# Sheet.net
KiCad netlist of a schematic drawn in Altium Designer
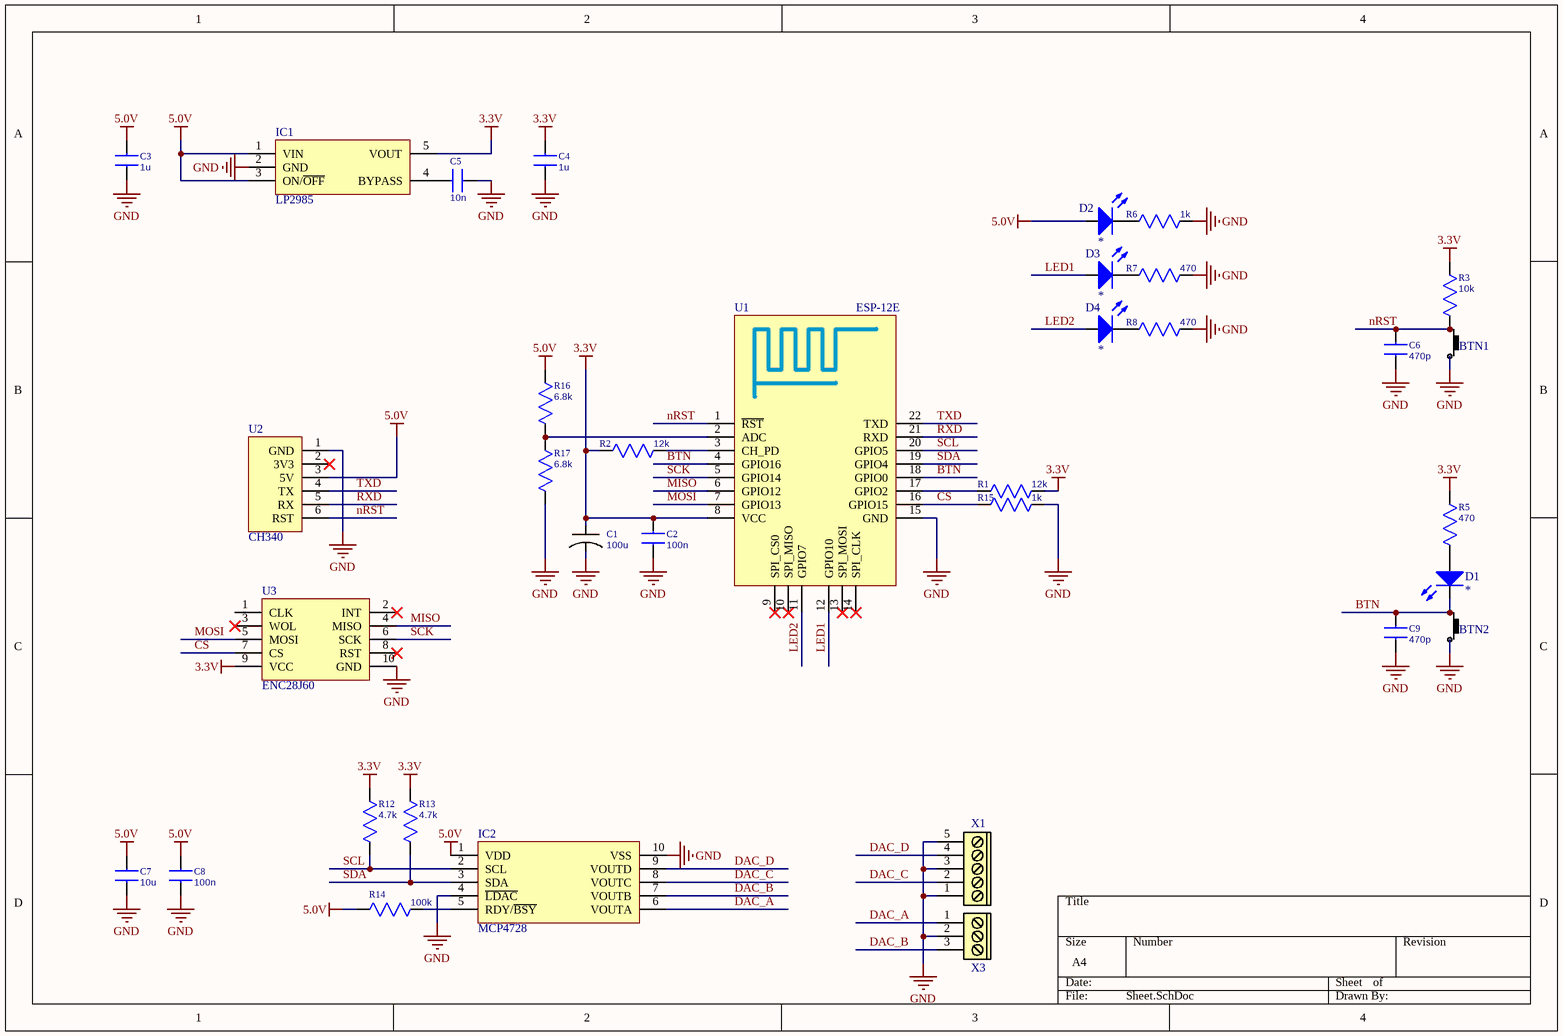
[diagram p0: Sheet.SchDoc]

(export (version "E")
  (design (tool "Eeschema 10.0.6"))
  (components
    (comp (ref "BTN1")
      (value "Push Button")
      (footprint "PUSH BUTTON RIGHT ANGLE")
      (description "Push button")
      (libsource (lib "Light_Music_Integrated_Library") (part "Push Button"))
    )
    (comp (ref "BTN2")
      (value "Push Button")
      (footprint "PUSH BUTTON RIGHT ANGLE")
      (description "Push button")
      (libsource (lib "") (part "Push Button_1"))
    )
    (comp (ref "C1")
      (value "100u")
      (footprint "R79")
      (description "Electrolit capasitor")
      (libsource (lib "SmartOutletIntegratedLibrary") (part "Electrolit"))
    )
    (comp (ref "C2")
      (value "100n")
      (footprint "C_0603")
      (description "Capacitor")
      (libsource (lib "AX_Altium_v2.3") (part "C0603"))
    )
    (comp (ref "C3")
      (value "1u")
      (footprint "C_0805")
      (description "Capacitor")
      (libsource (lib "AX_Altium_v2.3") (part "C0805"))
    )
    (comp (ref "C4")
      (value "1u")
      (footprint "C_0805")
      (description "Capacitor")
      (libsource (lib "AX_Altium_v2.3") (part "C0805"))
    )
    (comp (ref "C5")
      (value "10n")
      (footprint "C_0603")
      (description "Capacitor")
      (libsource (lib "AX_Altium_v2.3") (part "C0603"))
    )
    (comp (ref "C6")
      (value "470p")
      (footprint "C_0603")
      (description "Capacitor")
      (libsource (lib "AX_Altium_v2.3") (part "C0603"))
    )
    (comp (ref "C7")
      (value "10u")
      (footprint "C_0805")
      (description "Capacitor")
      (libsource (lib "AX_Altium_v2.3") (part "C0805"))
    )
    (comp (ref "C8")
      (value "100n")
      (footprint "C_0603")
      (description "Capacitor")
      (libsource (lib "AX_Altium_v2.3") (part "C0603"))
    )
    (comp (ref "C9")
      (value "470p")
      (footprint "C_0603")
      (description "Capacitor")
      (libsource (lib "AX_Altium_v2.3") (part "C0603"))
    )
    (comp (ref "D1")
      (value "*")
      (footprint "LED_5mm")
      (description "Typical INFRARED GaAs LED")
      (libsource (lib "AX_Altium_v2.3") (part "LED_5mm"))
    )
    (comp (ref "D2")
      (value "*")
      (footprint "LED_5mm")
      (description "Typical INFRARED GaAs LED")
      (libsource (lib "AX_Altium_v2.3") (part "LED_5mm"))
    )
    (comp (ref "D3")
      (value "*")
      (footprint "LED_5mm")
      (description "Typical INFRARED GaAs LED")
      (libsource (lib "AX_Altium_v2.3") (part "LED_5mm"))
    )
    (comp (ref "D4")
      (value "*")
      (footprint "LED_5mm")
      (description "Typical INFRARED GaAs LED")
      (libsource (lib "AX_Altium_v2.3") (part "LED_5mm"))
    )
    (comp (ref "IC1")
      (value "LP2985")
      (footprint "SOT23-5")
      (description "150-mA Low-noise Low-dropout Regulator With Shutdown")
      (libsource (lib "Schlib") (part "LP2985"))
    )
    (comp (ref "IC2")
      (value "MCP4728")
      (footprint "MSOP-10")
      (description "12-Bit, Quad Digital-to-Analog Converter with EEPROM Memory")
      (libsource (lib "TomatoBoardIntegrated_Library") (part "MCP4728"))
    )
    (comp (ref "R1")
      (value "12k")
      (footprint "R_0603")
      (description "Resistor")
      (libsource (lib "AX_Altium_v2.3") (part "R0603"))
    )
    (comp (ref "R2")
      (value "12k")
      (footprint "R_0603")
      (description "Resistor")
      (libsource (lib "AX_Altium_v2.3") (part "R0603"))
    )
    (comp (ref "R3")
      (value "10k")
      (footprint "R_0603")
      (description "Resistor")
      (libsource (lib "AX_Altium_v2.3") (part "R0603"))
    )
    (comp (ref "R5")
      (value "470")
      (footprint "R_0603")
      (description "Resistor")
      (libsource (lib "AX_Altium_v2.3") (part "R0603"))
    )
    (comp (ref "R6")
      (value "1k")
      (footprint "R_0603")
      (description "Resistor")
      (libsource (lib "AX_Altium_v2.3") (part "R0603"))
    )
    (comp (ref "R7")
      (value "470")
      (footprint "R_0603")
      (description "Resistor")
      (libsource (lib "AX_Altium_v2.3") (part "R0603"))
    )
    (comp (ref "R8")
      (value "470")
      (footprint "R_0603")
      (description "Resistor")
      (libsource (lib "AX_Altium_v2.3") (part "R0603"))
    )
    (comp (ref "R12")
      (value "4.7k")
      (footprint "R_0603")
      (description "Resistor")
      (libsource (lib "AX_Altium_v2.3") (part "R0603"))
    )
    (comp (ref "R13")
      (value "4.7k")
      (footprint "R_0603")
      (description "Resistor")
      (libsource (lib "AX_Altium_v2.3") (part "R0603"))
    )
    (comp (ref "R14")
      (value "100k")
      (footprint "R_0603")
      (description "Resistor")
      (libsource (lib "AX_Altium_v2.3") (part "R0603"))
    )
    (comp (ref "R15")
      (value "1k")
      (footprint "R_0603")
      (description "Resistor")
      (libsource (lib "AX_Altium_v2.3") (part "R0603"))
    )
    (comp (ref "R16")
      (value "6.8k")
      (footprint "R_0603")
      (description "Resistor")
      (libsource (lib "AX_Altium_v2.3") (part "R0603"))
    )
    (comp (ref "R17")
      (value "6.8k")
      (footprint "R_0603")
      (description "Resistor")
      (libsource (lib "AX_Altium_v2.3") (part "R0603"))
    )
    (comp (ref "U1")
      (value "ESP-12E")
      (footprint "ESP-12E")
      (description "WiFi Module")
      (libsource (lib "TomatoBoardIntegrated_Library") (part "ESP-12E"))
    )
    (comp (ref "U2")
      (value "CH340")
      (footprint "CH340")
      (description "USB to TTL UART CH340")
      (libsource (lib "TomatoBoardIntegrated_Library") (part "CH340"))
    )
    (comp (ref "U3")
      (value "ENC28J60")
      (footprint "ENC28J60")
      (description "ENC28J60 mini Ethernet module")
      (libsource (lib "TomatoBoardIntegrated_Library") (part "ENC28J60"))
    )
    (comp (ref "X1")
      (value "DG-300-5")
      (footprint "2EDGR-5.08-05P")
      (libsource (lib "Light_Music_Integrated_Library") (part "DG-300-5"))
    )
    (comp (ref "X3")
      (value "DG-300-3")
      (footprint "2EDGR-5.08-03P")
      (libsource (lib "Light_Music_Integrated_Library") (part "DG-300-3"))
    )
  )
  (nets
    (net (code "1") (name "/BTN") (class "Default")
      (node (ref "BTN2") (pin "2") (pinfunction "2_2") (pintype "passive"))
      (node (ref "C9") (pin "2") (pintype "passive"))
      (node (ref "D1") (pin "2") (pinfunction "K_2") (pintype "passive"))
      (node (ref "U1") (pin "18") (pinfunction "GPIO0_18") (pintype "passive"))
      (node (ref "U1") (pin "4") (pinfunction "GPIO16_4") (pintype "passive"))
    )
    (net (code "2") (name "/CS") (class "Default")
      (node (ref "R15") (pin "2") (pintype "passive"))
      (node (ref "U1") (pin "16") (pinfunction "GPIO15_16") (pintype "passive"))
      (node (ref "U3") (pin "7") (pinfunction "CS_7") (pintype "passive"))
    )
    (net (code "3") (name "/DAC_A") (class "Default")
      (node (ref "IC2") (pin "6") (pinfunction "VOUTA_6") (pintype "passive"))
      (node (ref "X3") (pin "1") (pinfunction "1_1") (pintype "passive"))
    )
    (net (code "4") (name "/DAC_B") (class "Default")
      (node (ref "IC2") (pin "7") (pinfunction "VOUTB_7") (pintype "passive"))
      (node (ref "X3") (pin "3") (pinfunction "3_3") (pintype "passive"))
    )
    (net (code "5") (name "/DAC_C") (class "Default")
      (node (ref "IC2") (pin "8") (pinfunction "VOUTC_8") (pintype "passive"))
      (node (ref "X1") (pin "2") (pinfunction "2_2") (pintype "passive"))
    )
    (net (code "6") (name "/DAC_D") (class "Default")
      (node (ref "IC2") (pin "9") (pinfunction "VOUTD_9") (pintype "passive"))
      (node (ref "X1") (pin "4") (pinfunction "4_4") (pintype "passive"))
    )
    (net (code "7") (name "/LED1") (class "Default")
      (node (ref "D3") (pin "1") (pinfunction "A_1") (pintype "passive"))
      (node (ref "U1") (pin "12") (pinfunction "GPIO10_12") (pintype "passive"))
    )
    (net (code "8") (name "/LED2") (class "Default")
      (node (ref "D4") (pin "1") (pinfunction "A_1") (pintype "passive"))
      (node (ref "U1") (pin "11") (pinfunction "GPIO7_11") (pintype "passive"))
    )
    (net (code "9") (name "/MISO") (class "Default")
      (node (ref "U1") (pin "6") (pinfunction "GPIO12_6") (pintype "passive"))
      (node (ref "U3") (pin "4") (pinfunction "MISO_4") (pintype "passive"))
    )
    (net (code "10") (name "/MOSI") (class "Default")
      (node (ref "U1") (pin "7") (pinfunction "GPIO13_7") (pintype "passive"))
      (node (ref "U3") (pin "5") (pinfunction "MOSI_5") (pintype "passive"))
    )
    (net (code "11") (name "/RXD") (class "Default")
      (node (ref "U1") (pin "21") (pinfunction "RXD_21") (pintype "passive"))
      (node (ref "U2") (pin "5") (pinfunction "RX_5") (pintype "passive"))
    )
    (net (code "12") (name "/SCK") (class "Default")
      (node (ref "U1") (pin "5") (pinfunction "GPIO14_5") (pintype "passive"))
      (node (ref "U3") (pin "6") (pinfunction "SCK_6") (pintype "passive"))
    )
    (net (code "13") (name "/SCL") (class "Default")
      (node (ref "IC2") (pin "2") (pinfunction "SCL_2") (pintype "passive"))
      (node (ref "R12") (pin "2") (pintype "passive"))
      (node (ref "U1") (pin "20") (pinfunction "GPIO5_20") (pintype "passive"))
    )
    (net (code "14") (name "/SDA") (class "Default")
      (node (ref "IC2") (pin "3") (pinfunction "SDA_3") (pintype "passive"))
      (node (ref "R13") (pin "2") (pintype "passive"))
      (node (ref "U1") (pin "19") (pinfunction "GPIO4_19") (pintype "passive"))
    )
    (net (code "15") (name "/TXD") (class "Default")
      (node (ref "U1") (pin "22") (pinfunction "TXD_22") (pintype "passive"))
      (node (ref "U2") (pin "4") (pinfunction "TX_4") (pintype "passive"))
    )
    (net (code "16") (name "/nRST") (class "Default")
      (node (ref "BTN1") (pin "1") (pinfunction "1_1") (pintype "passive"))
      (node (ref "C6") (pin "2") (pintype "passive"))
      (node (ref "R3") (pin "2") (pintype "passive"))
      (node (ref "U1") (pin "1") (pinfunction "~{RST}_1") (pintype "passive"))
      (node (ref "U2") (pin "6") (pinfunction "RST_6") (pintype "passive"))
    )
    (net (code "17") (name "3.3V") (class "Default")
      (node (ref "C1") (pin "1") (pinfunction "1_1") (pintype "passive"))
      (node (ref "C2") (pin "1") (pintype "passive"))
      (node (ref "C4") (pin "2") (pintype "passive"))
      (node (ref "IC1") (pin "5") (pinfunction "VOUT_5") (pintype "passive"))
      (node (ref "R1") (pin "1") (pintype "passive"))
      (node (ref "R12") (pin "1") (pintype "passive"))
      (node (ref "R13") (pin "1") (pintype "passive"))
      (node (ref "R2") (pin "2") (pintype "passive"))
      (node (ref "R3") (pin "1") (pintype "passive"))
      (node (ref "R5") (pin "1") (pintype "passive"))
      (node (ref "U1") (pin "8") (pinfunction "VCC_8") (pintype "passive"))
      (node (ref "U3") (pin "9") (pinfunction "VCC_9") (pintype "passive"))
    )
    (net (code "18") (name "5.0V") (class "Default")
      (node (ref "C3") (pin "2") (pintype "passive"))
      (node (ref "C7") (pin "2") (pintype "passive"))
      (node (ref "C8") (pin "1") (pintype "passive"))
      (node (ref "D2") (pin "1") (pinfunction "A_1") (pintype "passive"))
      (node (ref "IC1") (pin "1") (pinfunction "VIN_1") (pintype "passive"))
      (node (ref "IC1") (pin "3") (pinfunction "ON/~{OFF}_3") (pintype "passive"))
      (node (ref "IC2") (pin "1") (pinfunction "VDD_1") (pintype "passive"))
      (node (ref "R14") (pin "1") (pintype "passive"))
      (node (ref "R16") (pin "2") (pintype "passive"))
      (node (ref "U2") (pin "3") (pinfunction "5V_3") (pintype "passive"))
    )
    (net (code "19") (name "GND") (class "Default")
      (node (ref "BTN1") (pin "2") (pinfunction "2_2") (pintype "passive"))
      (node (ref "BTN2") (pin "1") (pinfunction "1_1") (pintype "passive"))
      (node (ref "C1") (pin "2") (pinfunction "2_2") (pintype "passive"))
      (node (ref "C2") (pin "2") (pintype "passive"))
      (node (ref "C3") (pin "1") (pintype "passive"))
      (node (ref "C4") (pin "1") (pintype "passive"))
      (node (ref "C5") (pin "1") (pintype "passive"))
      (node (ref "C6") (pin "1") (pintype "passive"))
      (node (ref "C7") (pin "1") (pintype "passive"))
      (node (ref "C8") (pin "2") (pintype "passive"))
      (node (ref "C9") (pin "1") (pintype "passive"))
      (node (ref "IC1") (pin "2") (pinfunction "GND_2") (pintype "passive"))
      (node (ref "IC2") (pin "10") (pinfunction "VSS_10") (pintype "passive"))
      (node (ref "IC2") (pin "4") (pinfunction "~{LDAC}_4") (pintype "passive"))
      (node (ref "R15") (pin "1") (pintype "passive"))
      (node (ref "R17") (pin "1") (pintype "passive"))
      (node (ref "R6") (pin "1") (pintype "passive"))
      (node (ref "R7") (pin "1") (pintype "passive"))
      (node (ref "R8") (pin "1") (pintype "passive"))
      (node (ref "U1") (pin "15") (pinfunction "GND_15") (pintype "passive"))
      (node (ref "U2") (pin "1") (pinfunction "GND_1") (pintype "passive"))
      (node (ref "U3") (pin "10") (pinfunction "GND_10") (pintype "passive"))
      (node (ref "X1") (pin "1") (pinfunction "1_1") (pintype "passive"))
      (node (ref "X1") (pin "3") (pinfunction "3_3") (pintype "passive"))
      (node (ref "X1") (pin "5") (pinfunction "5_5") (pintype "passive"))
      (node (ref "X3") (pin "2") (pinfunction "2_2") (pintype "passive"))
    )
    (net (code "20") (name "Net-(D1-A)") (class "Default")
      (node (ref "D1") (pin "1") (pinfunction "A_1") (pintype "passive"))
      (node (ref "R5") (pin "2") (pintype "passive"))
    )
    (net (code "21") (name "Net-(D2-K)") (class "Default")
      (node (ref "D2") (pin "2") (pinfunction "K_2") (pintype "passive"))
      (node (ref "R6") (pin "2") (pintype "passive"))
    )
    (net (code "22") (name "Net-(D3-K)") (class "Default")
      (node (ref "D3") (pin "2") (pinfunction "K_2") (pintype "passive"))
      (node (ref "R7") (pin "2") (pintype "passive"))
    )
    (net (code "23") (name "Net-(D4-K)") (class "Default")
      (node (ref "D4") (pin "2") (pinfunction "K_2") (pintype "passive"))
      (node (ref "R8") (pin "2") (pintype "passive"))
    )
    (net (code "24") (name "Net-(IC1-BYPASS)") (class "Default")
      (node (ref "C5") (pin "2") (pintype "passive"))
      (node (ref "IC1") (pin "4") (pinfunction "BYPASS_4") (pintype "passive"))
    )
    (net (code "25") (name "Net-(IC2-RDY{slash}~{BSY})") (class "Default")
      (node (ref "IC2") (pin "5") (pinfunction "RDY/~{BSY}_5") (pintype "passive"))
      (node (ref "R14") (pin "2") (pintype "passive"))
    )
    (net (code "26") (name "Net-(U1-ADC)") (class "Default")
      (node (ref "R16") (pin "1") (pintype "passive"))
      (node (ref "R17") (pin "2") (pintype "passive"))
      (node (ref "U1") (pin "2") (pinfunction "ADC_2") (pintype "passive"))
    )
    (net (code "27") (name "Net-(U1-CH_PD)") (class "Default")
      (node (ref "R2") (pin "1") (pintype "passive"))
      (node (ref "U1") (pin "3") (pinfunction "CH_PD_3") (pintype "passive"))
    )
    (net (code "28") (name "Net-(U1-GPIO2)") (class "Default")
      (node (ref "R1") (pin "2") (pintype "passive"))
      (node (ref "U1") (pin "17") (pinfunction "GPIO2_17") (pintype "passive"))
    )
    (net (code "29") (name "unconnected-(U1-SPI_CLK-Pad14)") (class "Default")
      (node (ref "U1") (pin "14") (pinfunction "SPI_CLK_14") (pintype "passive+no_connect"))
    )
    (net (code "30") (name "unconnected-(U1-SPI_CS0-Pad9)") (class "Default")
      (node (ref "U1") (pin "9") (pinfunction "SPI_CS0_9") (pintype "passive+no_connect"))
    )
    (net (code "31") (name "unconnected-(U1-SPI_MISO-Pad10)") (class "Default")
      (node (ref "U1") (pin "10") (pinfunction "SPI_MISO_10") (pintype "passive+no_connect"))
    )
    (net (code "32") (name "unconnected-(U1-SPI_MOSI-Pad13)") (class "Default")
      (node (ref "U1") (pin "13") (pinfunction "SPI_MOSI_13") (pintype "passive+no_connect"))
    )
    (net (code "33") (name "unconnected-(U2-3V3-Pad2)") (class "Default")
      (node (ref "U2") (pin "2") (pinfunction "3V3_2") (pintype "passive+no_connect"))
    )
    (net (code "34") (name "unconnected-(U3-CLK-Pad1)") (class "Default")
      (node (ref "U3") (pin "1") (pinfunction "CLK_1") (pintype "passive"))
    )
    (net (code "35") (name "unconnected-(U3-INT-Pad2)") (class "Default")
      (node (ref "U3") (pin "2") (pinfunction "INT_2") (pintype "passive+no_connect"))
    )
    (net (code "36") (name "unconnected-(U3-RST-Pad8)") (class "Default")
      (node (ref "U3") (pin "8") (pinfunction "RST_8") (pintype "passive+no_connect"))
    )
    (net (code "37") (name "unconnected-(U3-WOL-Pad3)") (class "Default")
      (node (ref "U3") (pin "3") (pinfunction "WOL_3") (pintype "passive+no_connect"))
    )
  )
)
